# mosfet_cutoff.net
KiCad netlist of a schematic drawn in EAGLE
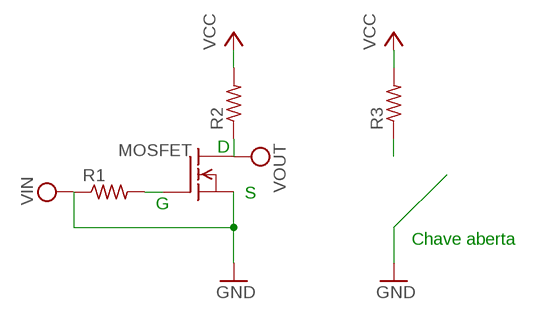
[diagram p0: schematic, sheet 1]

(export (version "E")
  (design (tool "Eeschema 10.0.6"))
  (components
    (comp (ref "MOSFET")
      (value "BSS97")
      (footprint "eagle-import:TO202")
      (libsource (lib "eagle-import") (part "BSS97"))
    )
    (comp (ref "R1")
      (value "R-US_0204/2V")
      (footprint "eagle-import:0204V")
      (libsource (lib "eagle-import") (part "R-US_0204/2V"))
    )
    (comp (ref "R2")
      (value "R-US_0204/2V")
      (footprint "eagle-import:0204V")
      (libsource (lib "eagle-import") (part "R-US_0204/2V"))
    )
    (comp (ref "R3")
      (value "R-US_0204/2V")
      (footprint "eagle-import:0204V")
      (libsource (lib "eagle-import") (part "R-US_0204/2V"))
    )
  )
  (nets
    (net (code "1") (name "GND") (class "Default")
      (node (ref "MOSFET") (pin "1") (pinfunction "S_1") (pintype "passive"))
      (node (ref "R1") (pin "1") (pinfunction "1_1") (pintype "passive"))
    )
    (net (code "2") (name "Net-(MOSFET-D)") (class "Default")
      (node (ref "MOSFET") (pin "2") (pinfunction "D_2") (pintype "passive"))
      (node (ref "R2") (pin "1") (pinfunction "1_1") (pintype "passive"))
    )
    (net (code "3") (name "Net-(MOSFET-G)") (class "Default")
      (node (ref "MOSFET") (pin "3") (pinfunction "G_3") (pintype "passive"))
      (node (ref "R1") (pin "2") (pinfunction "2_2") (pintype "passive"))
    )
    (net (code "4") (name "VCC") (class "Default")
      (node (ref "R2") (pin "2") (pinfunction "2_2") (pintype "passive"))
      (node (ref "R3") (pin "2") (pinfunction "2_2") (pintype "passive"))
    )
    (net (code "7") (name "unconnected-(R3-Pad1)") (class "Default")
      (node (ref "R3") (pin "1") (pinfunction "1_1") (pintype "passive"))
    )
  )
)
